# obd_driver_module.net
KiCad netlist of a schematic drawn in EAGLE
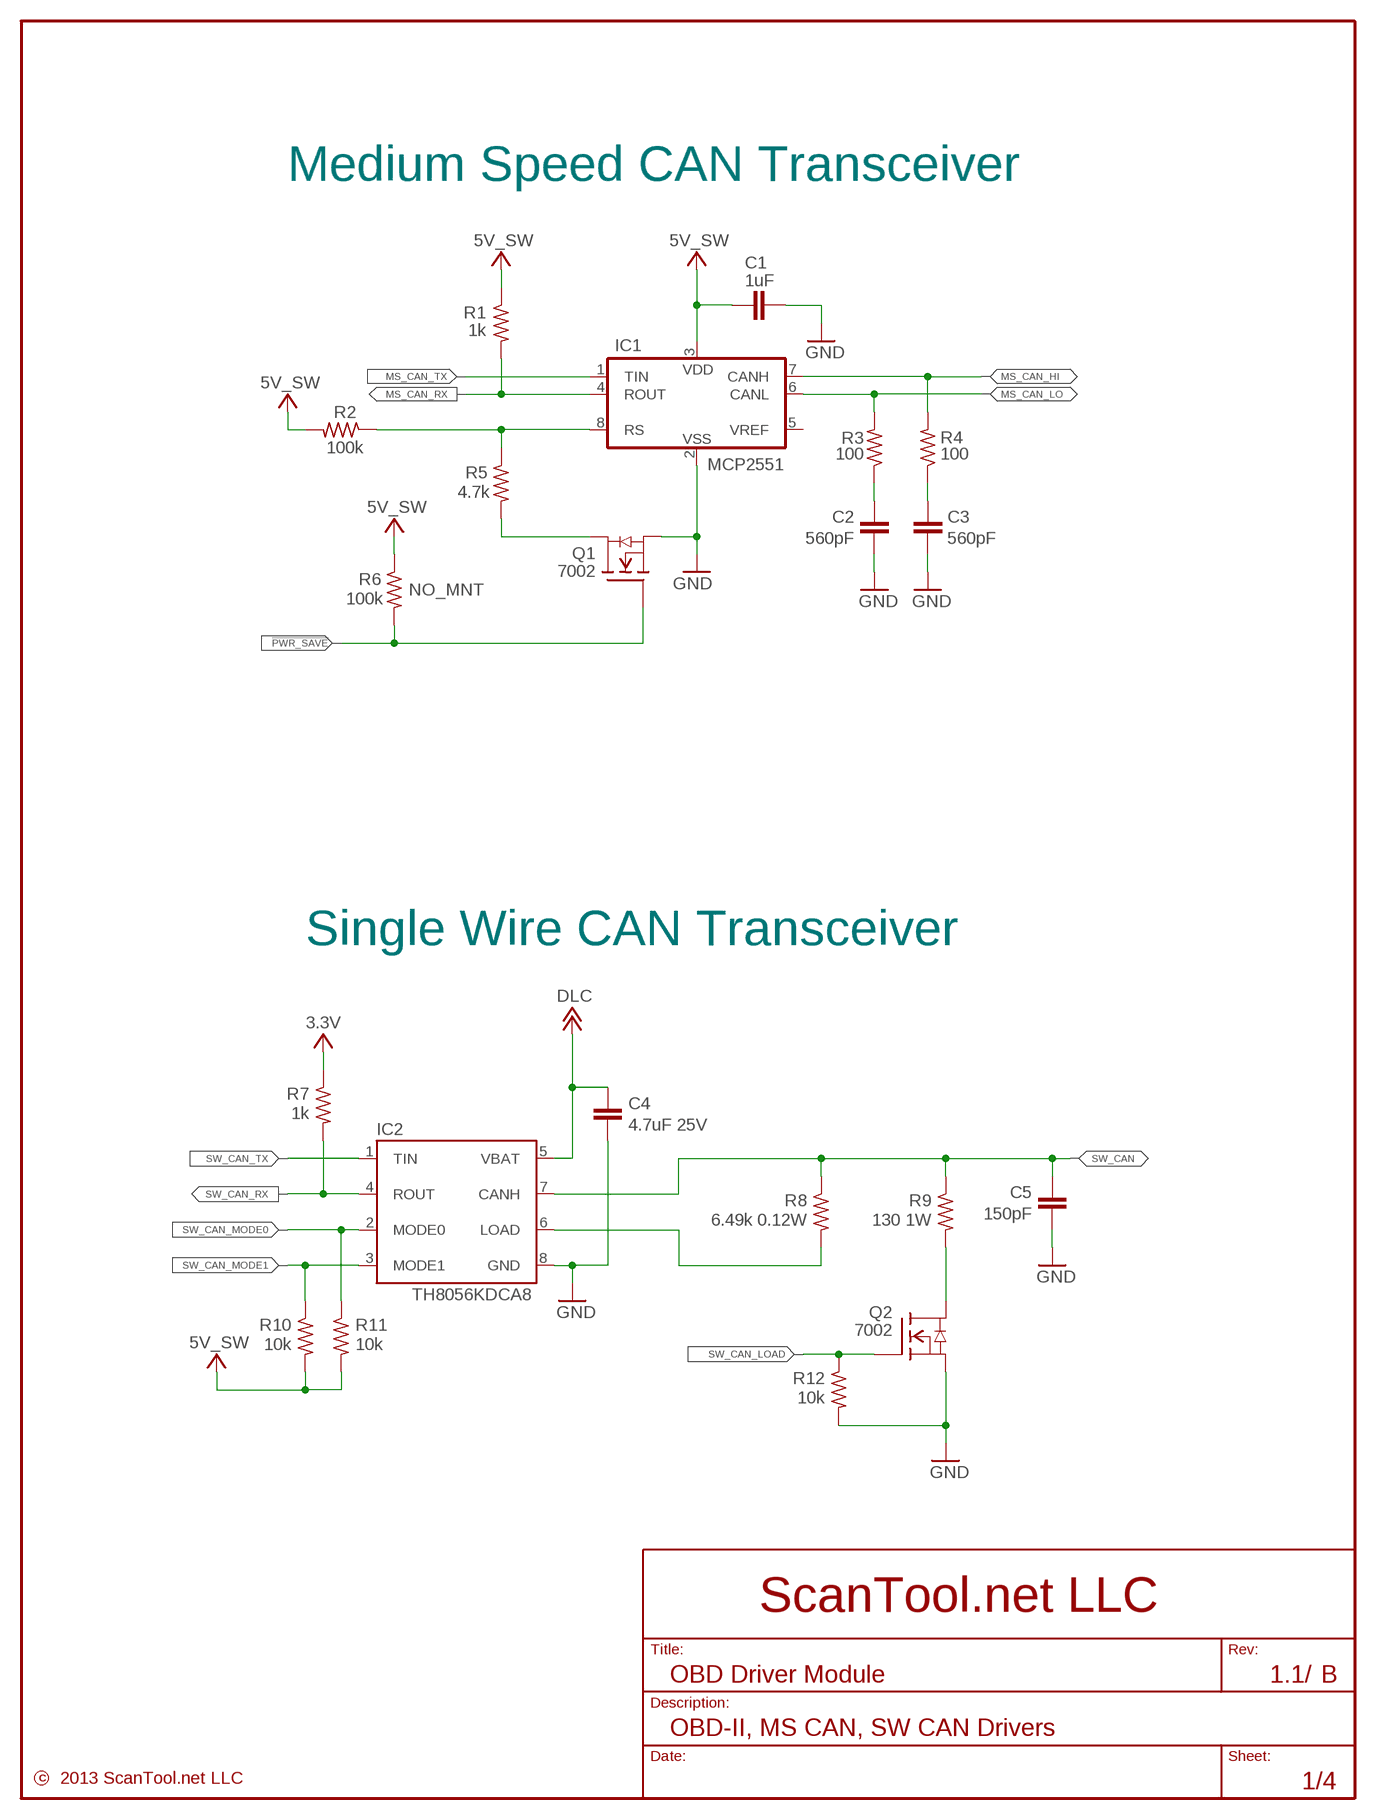
[diagram p0: schematic, sheet 1]
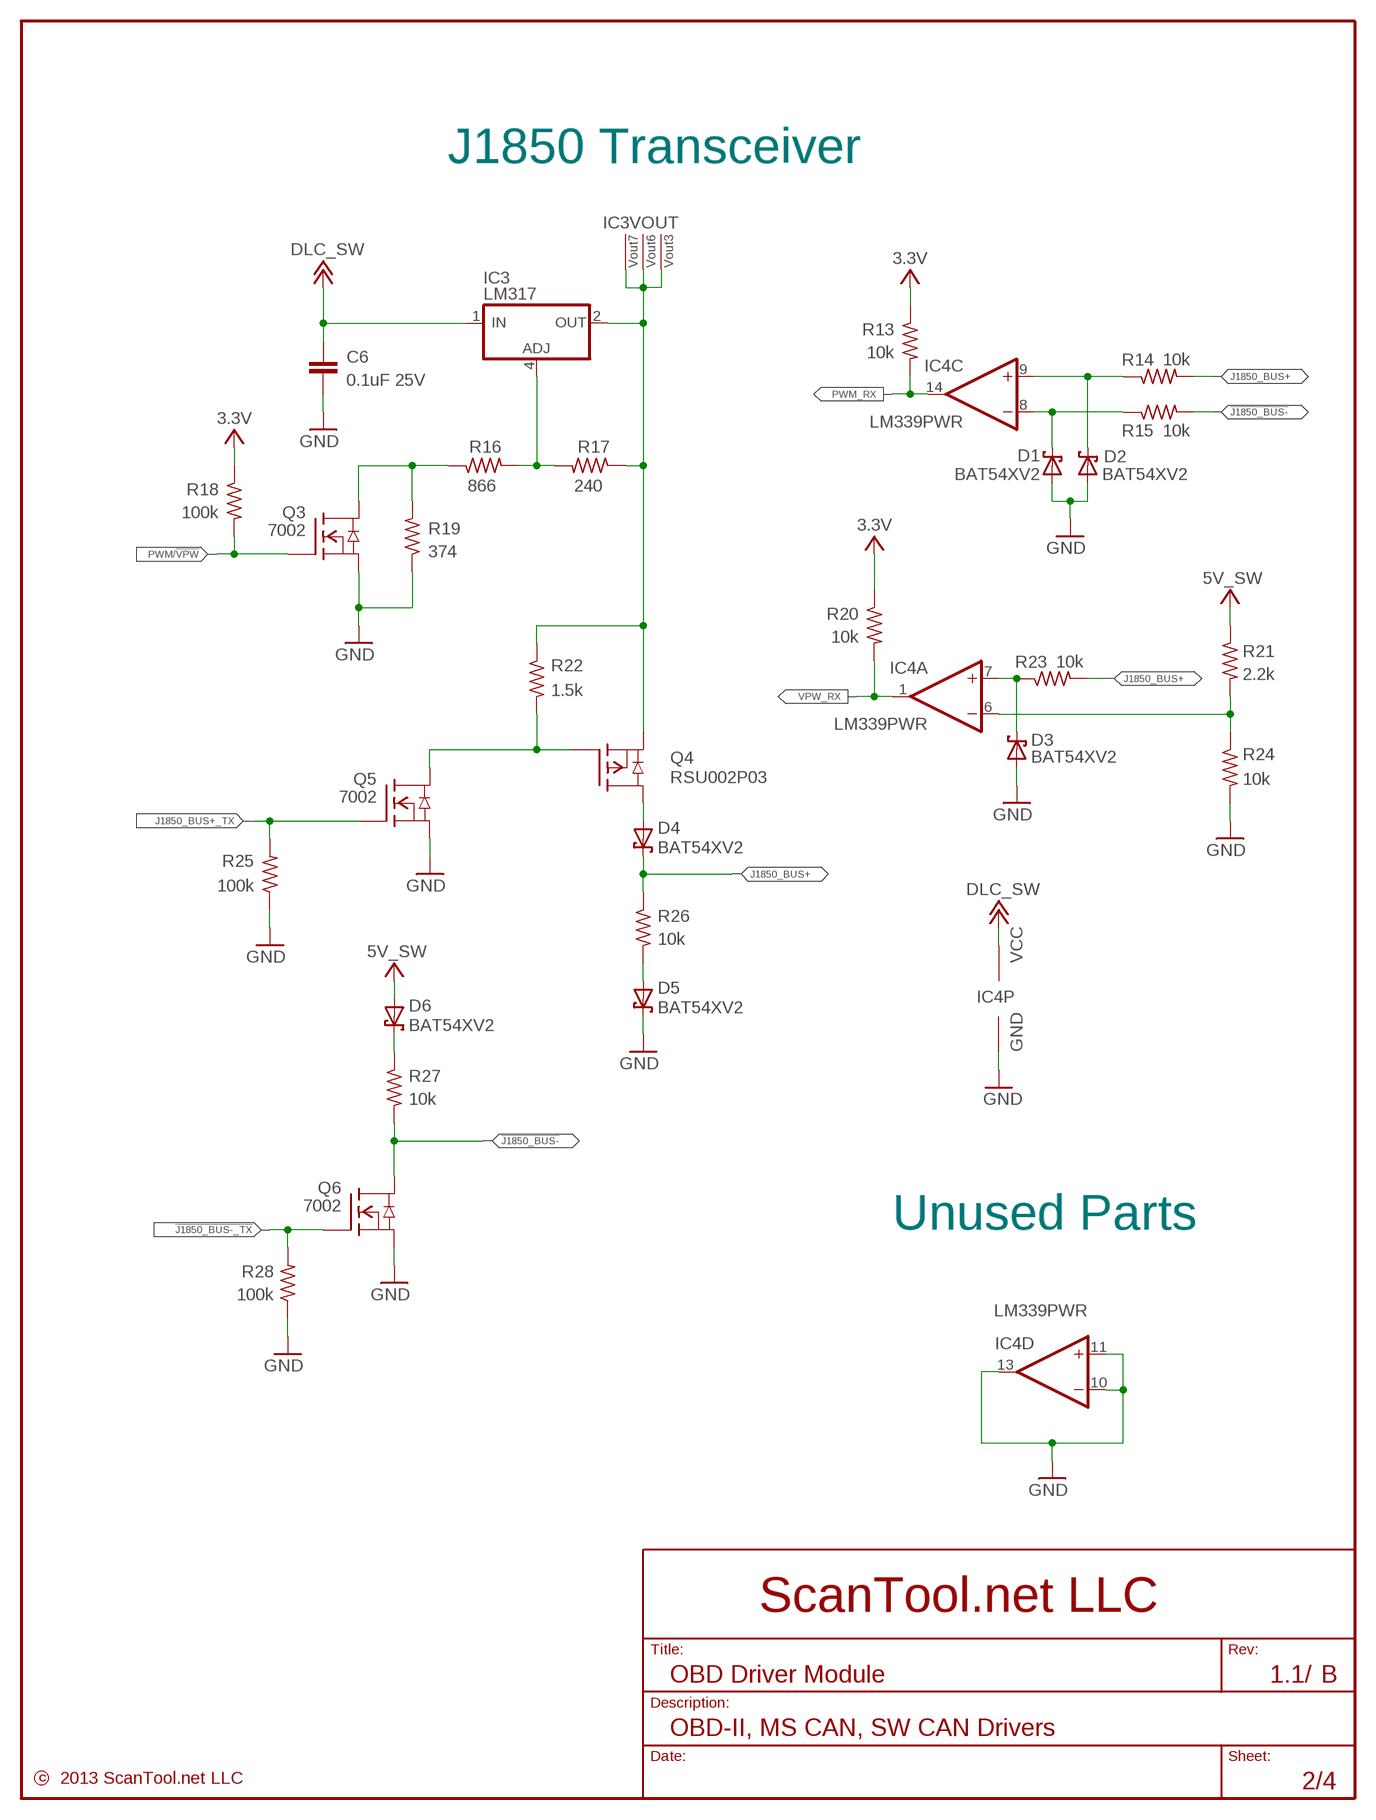
[diagram p1: schematic, sheet 2]
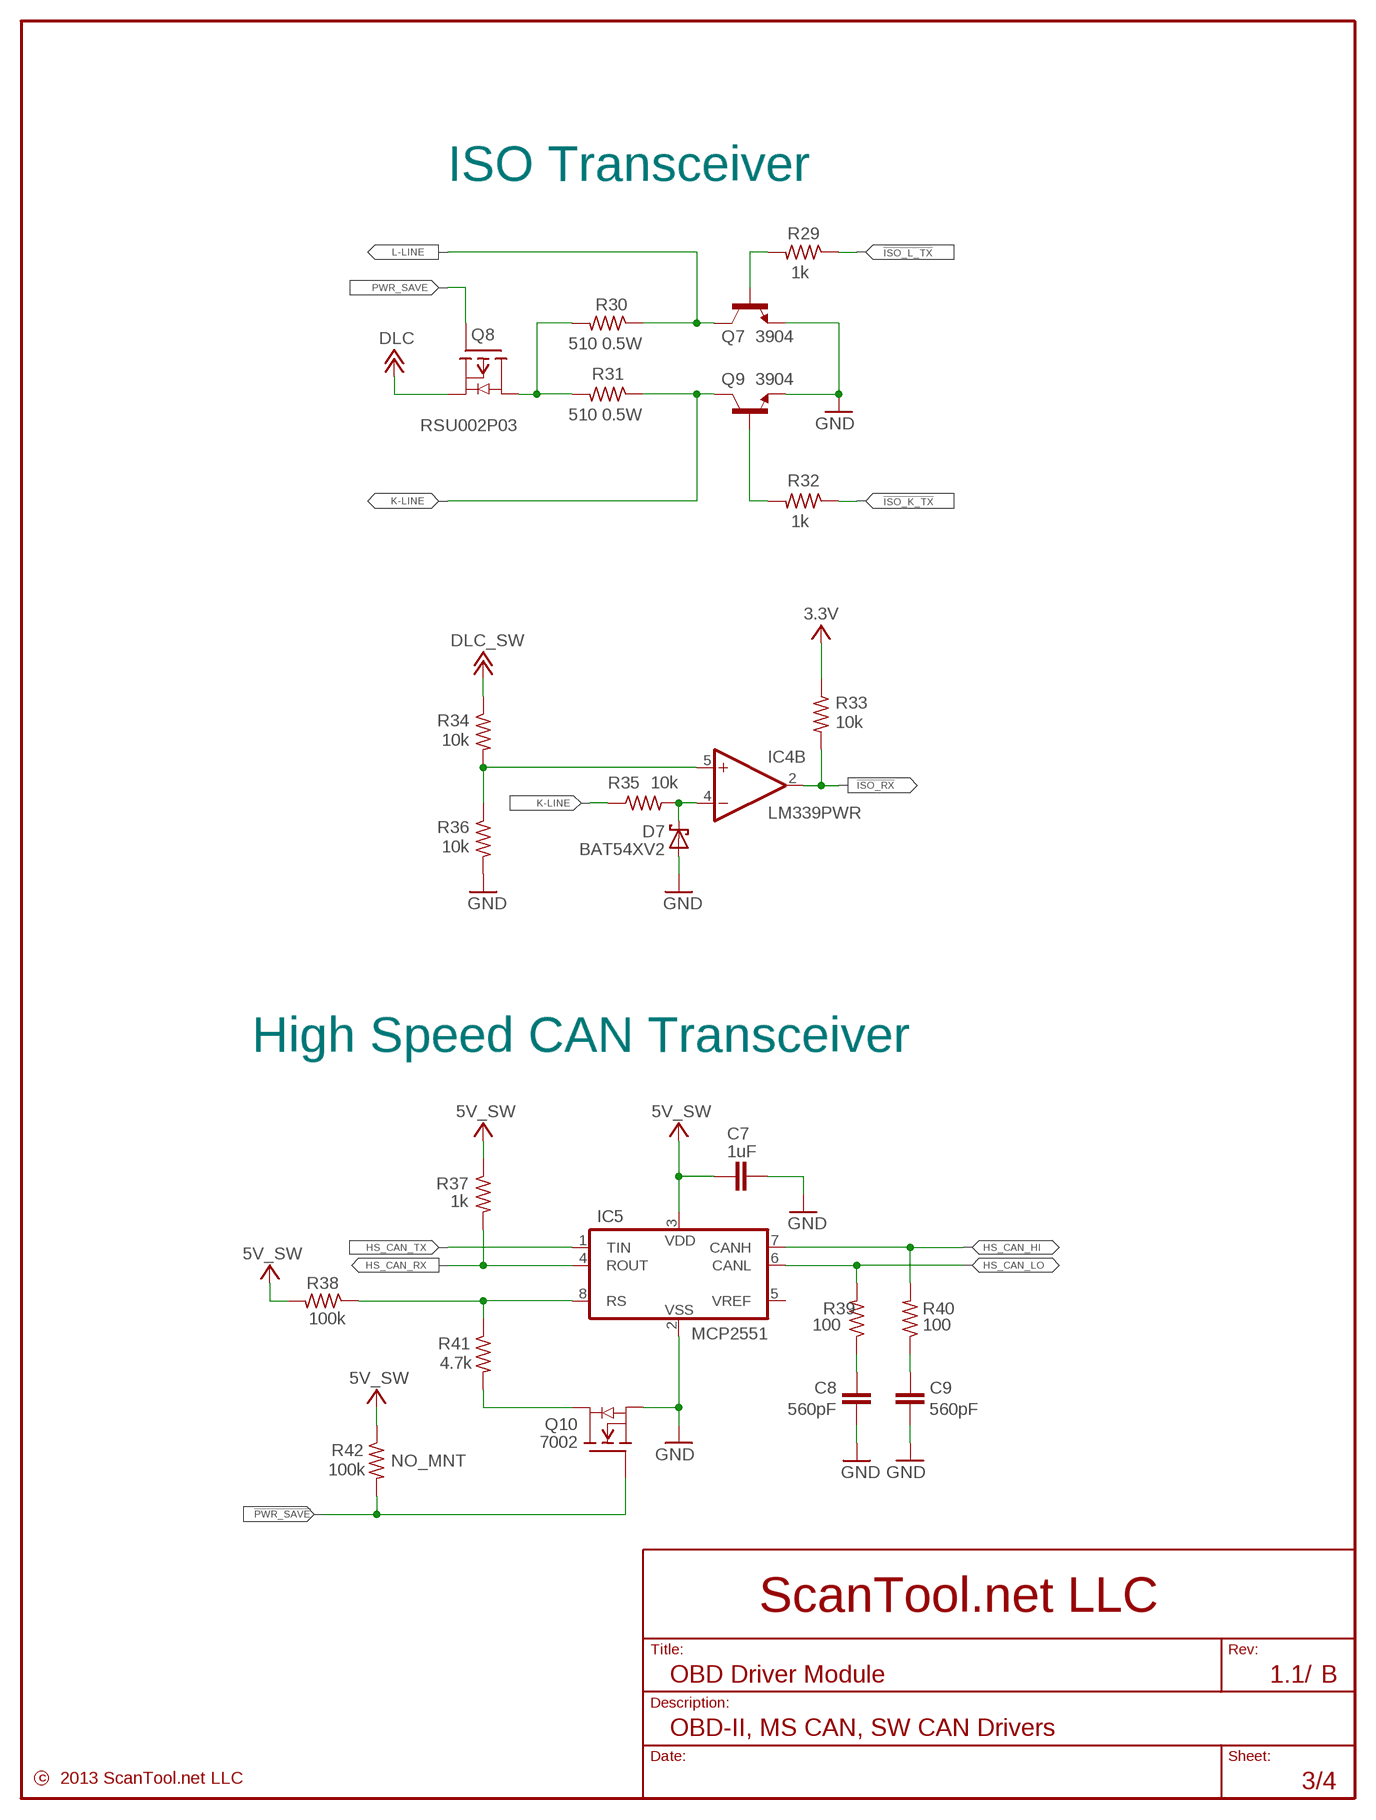
[diagram p2: schematic, sheet 3]
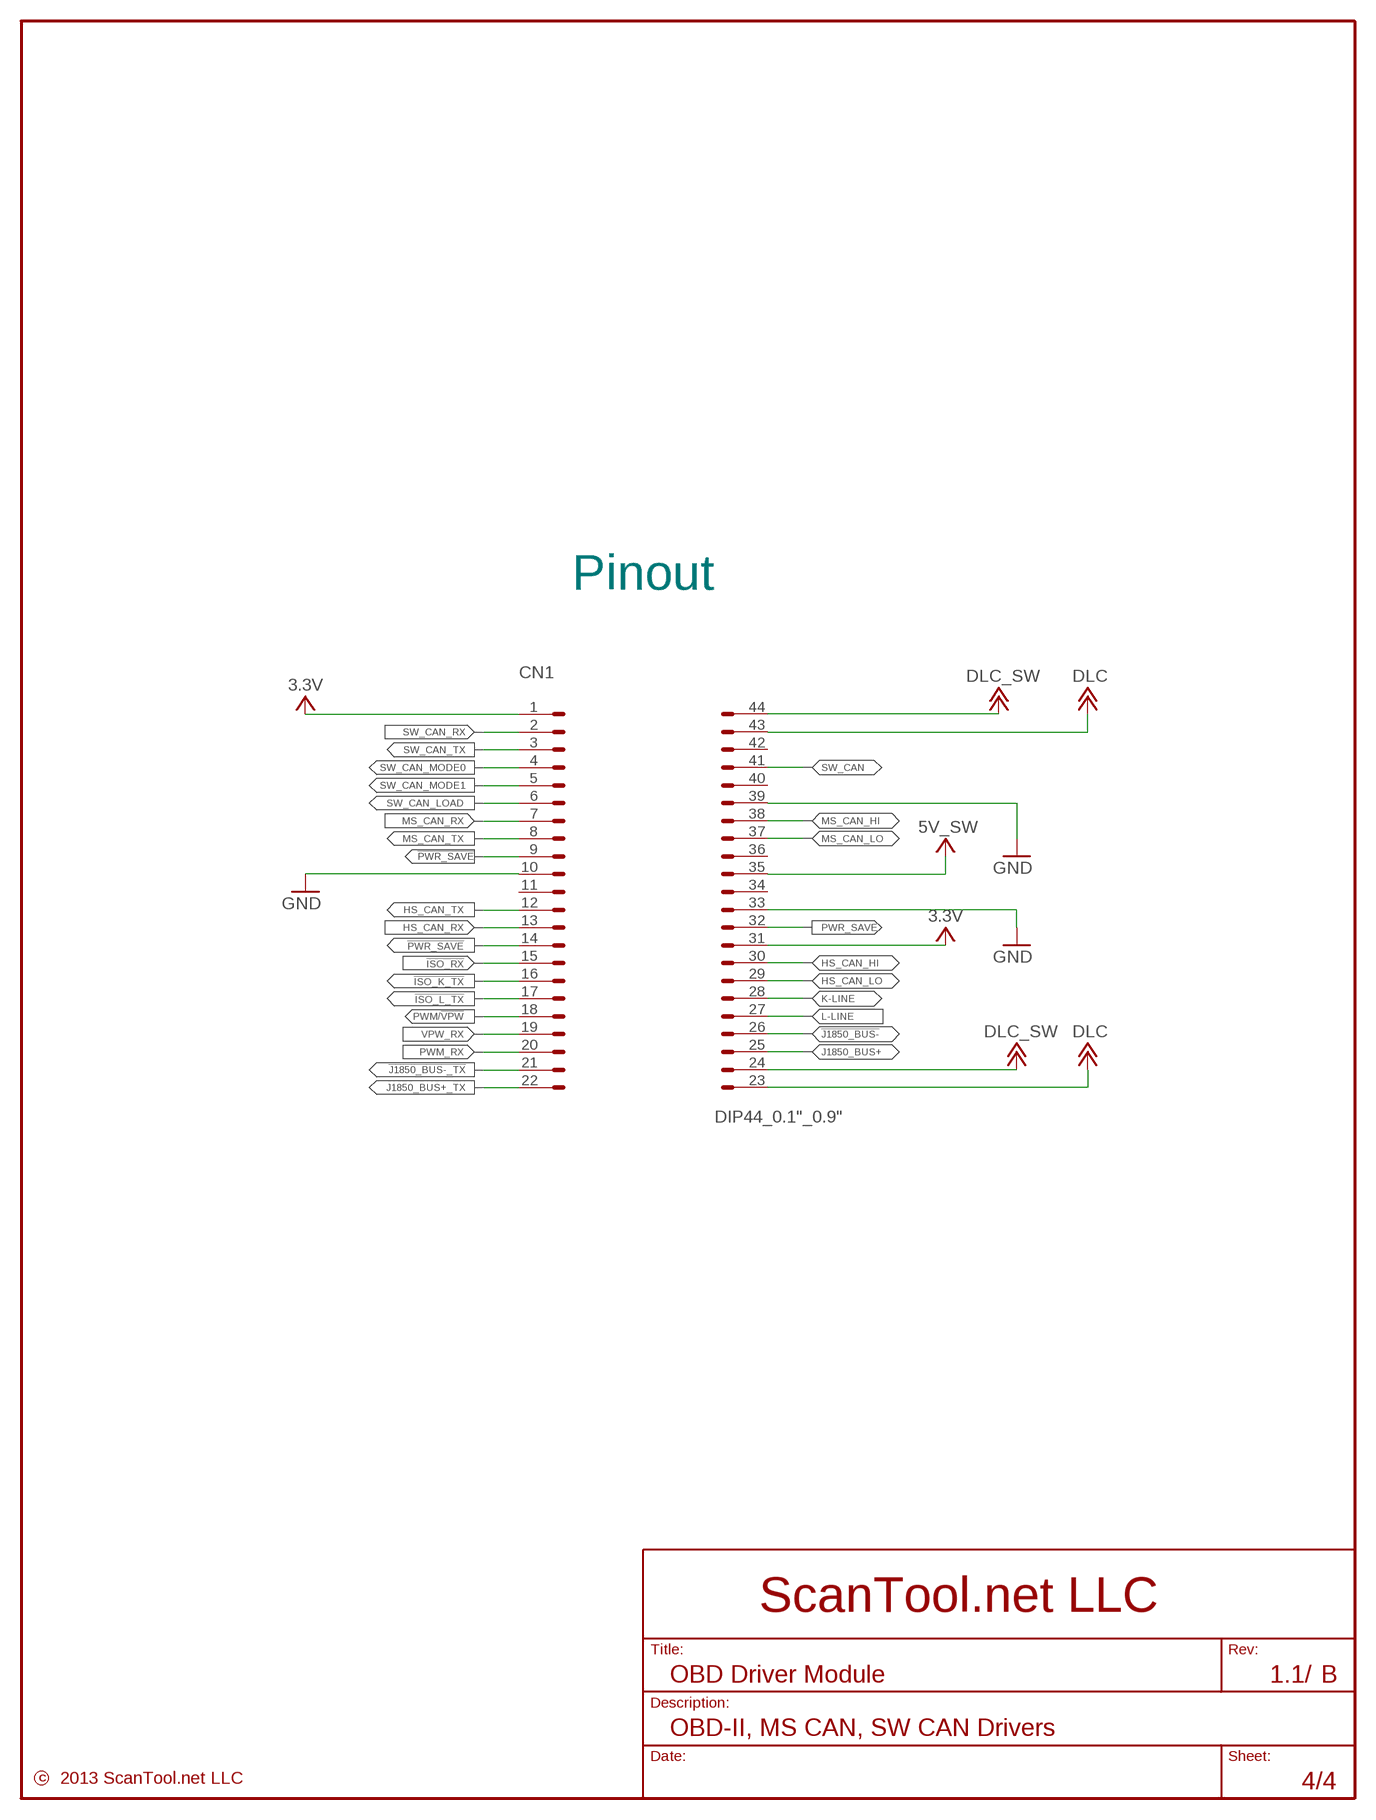
[diagram p3: schematic, sheet 4]

(export (version "E")
  (design (tool "Eeschema 10.0.6"))
  (components
    (comp (ref "C1")
      (value "1uF")
      (footprint "eagle-import:0603")
      (libsource (lib "eagle-import") (part "C-EU_0603"))
    )
    (comp (ref "C2")
      (value "560pF")
      (footprint "eagle-import:0603")
      (libsource (lib "eagle-import") (part "C-EU_0603"))
    )
    (comp (ref "C3")
      (value "560pF")
      (footprint "eagle-import:0603")
      (libsource (lib "eagle-import") (part "C-EU_0603"))
    )
    (comp (ref "C4")
      (value "4.7uF 25V")
      (footprint "eagle-import:0805")
      (libsource (lib "eagle-import") (part "C-EU_0805"))
    )
    (comp (ref "C5")
      (value "150pF")
      (footprint "eagle-import:0603")
      (libsource (lib "eagle-import") (part "C-EU_0603"))
    )
    (comp (ref "IC1")
      (value "MCP2551")
      (footprint "eagle-import:SO-8")
      (fields (field (name "PARTNUM") "MCP2551-I/SN"))
      (libsource (lib "eagle-import") (part "MCP2551-I/SN"))
    )
    (comp (ref "IC2")
      (value "TH8056KDCA8")
      (footprint "eagle-import:SO-8")
      (libsource (lib "eagle-import") (part "TH8056KDCA8"))
    )
    (comp (ref "Q1")
      (value "7002")
      (footprint "eagle-import:SOT323-3")
      (fields
        (field (name "PARTNUM") "2N7002WT1G")
        (field (name "MANUF") "ON Semiconductor")
        (field (name "PARTNUM_1") "2N7002WT1G")
        (field (name "SUPPLIER") "Digikey:2N7002WT1GOSCT-ND")
      )
      (libsource (lib "eagle-import") (part "2N7002W"))
    )
    (comp (ref "Q2")
      (value "7002")
      (footprint "eagle-import:SOT323-3")
      (fields
        (field (name "PARTNUM") "2N7002WT1G")
        (field (name "MANUF") "ON Semiconductor")
        (field (name "PARTNUM_1") "2N7002WT1G")
        (field (name "SUPPLIER") "Digikey:2N7002WT1GOSCT-ND")
      )
      (libsource (lib "eagle-import") (part "2N7002W"))
    )
    (comp (ref "R1")
      (value "1k")
      (footprint "eagle-import:0603")
      (libsource (lib "eagle-import") (part "R-US_0603"))
    )
    (comp (ref "R2")
      (value "100k")
      (footprint "eagle-import:0603")
      (libsource (lib "eagle-import") (part "R-US_0603"))
    )
    (comp (ref "R3")
      (value "100")
      (footprint "eagle-import:0603")
      (libsource (lib "eagle-import") (part "R-US_0603"))
    )
    (comp (ref "R4")
      (value "100")
      (footprint "eagle-import:0603")
      (libsource (lib "eagle-import") (part "R-US_0603"))
    )
    (comp (ref "R5")
      (value "4.7k")
      (footprint "eagle-import:0603")
      (libsource (lib "eagle-import") (part "R-US_0603"))
    )
    (comp (ref "R6")
      (value "100k")
      (footprint "eagle-import:0603")
      (libsource (lib "eagle-import") (part "R-US_0603"))
    )
    (comp (ref "R7")
      (value "1k")
      (footprint "eagle-import:0603")
      (libsource (lib "eagle-import") (part "R-US_0603"))
    )
    (comp (ref "R8")
      (value "6.49k 0.12W")
      (footprint "eagle-import:0603")
      (libsource (lib "eagle-import") (part "R-US_0603"))
    )
    (comp (ref "R9")
      (value "130 1W")
      (footprint "eagle-import:2512")
      (libsource (lib "eagle-import") (part "R-US_2512"))
    )
    (comp (ref "R10")
      (value "10k")
      (footprint "eagle-import:0603")
      (libsource (lib "eagle-import") (part "R-US_0603"))
    )
    (comp (ref "R11")
      (value "10k")
      (footprint "eagle-import:0603")
      (libsource (lib "eagle-import") (part "R-US_0603"))
    )
    (comp (ref "R12")
      (value "10k")
      (footprint "eagle-import:0603")
      (libsource (lib "eagle-import") (part "R-US_0603"))
    )
    (comp (ref "C7")
      (value "1uF")
      (footprint "eagle-import:0603")
      (libsource (lib "eagle-import") (part "C-EU_0603"))
    )
    (comp (ref "C8")
      (value "560pF")
      (footprint "eagle-import:0603")
      (libsource (lib "eagle-import") (part "C-EU_0603"))
    )
    (comp (ref "C9")
      (value "560pF")
      (footprint "eagle-import:0603")
      (libsource (lib "eagle-import") (part "C-EU_0603"))
    )
    (comp (ref "D7")
      (value "BAT54XV2")
      (footprint "eagle-import:SOD-523F")
      (libsource (lib "eagle-import") (part "BAT54XV2"))
    )
    (comp (ref "IC4")
      (value "LM339PWR")
      (footprint "eagle-import:TSSOP-14")
      (libsource (lib "eagle-import") (part "LM339PWR"))
    )
    (comp (ref "IC5")
      (value "MCP2551")
      (footprint "eagle-import:SO-8")
      (fields (field (name "PARTNUM") "MCP2551-I/SN"))
      (libsource (lib "eagle-import") (part "MCP2551-I/SN"))
    )
    (comp (ref "Q7")
      (value "3904")
      (footprint "eagle-import:SOT323-3")
      (fields (field (name "PARTNUM") "MMBT3904WT1G"))
      (libsource (lib "eagle-import") (part "?3904MMST"))
    )
    (comp (ref "Q8")
      (value "RSU002P03")
      (footprint "eagle-import:SOT323-3")
      (fields (field (name "PARTNUM") "RSU002P03T106"))
      (libsource (lib "eagle-import") (part "RSU002P03"))
    )
    (comp (ref "Q9")
      (value "3904")
      (footprint "eagle-import:SOT323-3")
      (fields (field (name "PARTNUM") "MMBT3904WT1G"))
      (libsource (lib "eagle-import") (part "?3904MMST"))
    )
    (comp (ref "Q10")
      (value "7002")
      (footprint "eagle-import:SOT323-3")
      (fields
        (field (name "PARTNUM") "2N7002WT1G")
        (field (name "MANUF") "ON Semiconductor")
        (field (name "PARTNUM_1") "2N7002WT1G")
        (field (name "SUPPLIER") "Digikey:2N7002WT1GOSCT-ND")
      )
      (libsource (lib "eagle-import") (part "2N7002W"))
    )
    (comp (ref "R29")
      (value "1k")
      (footprint "eagle-import:0603")
      (libsource (lib "eagle-import") (part "R-US_0603"))
    )
    (comp (ref "R30")
      (value "510 0.5W")
      (footprint "eagle-import:1210")
      (libsource (lib "eagle-import") (part "R-US_1210"))
    )
    (comp (ref "R31")
      (value "510 0.5W")
      (footprint "eagle-import:1210")
      (libsource (lib "eagle-import") (part "R-US_1210"))
    )
    (comp (ref "R32")
      (value "1k")
      (footprint "eagle-import:0603")
      (libsource (lib "eagle-import") (part "R-US_0603"))
    )
    (comp (ref "R33")
      (value "10k")
      (footprint "eagle-import:0603")
      (libsource (lib "eagle-import") (part "R-US_0603"))
    )
    (comp (ref "R34")
      (value "10k")
      (footprint "eagle-import:0603")
      (libsource (lib "eagle-import") (part "R-US_0603"))
    )
    (comp (ref "R35")
      (value "10k")
      (footprint "eagle-import:0603")
      (libsource (lib "eagle-import") (part "R-US_0603"))
    )
    (comp (ref "R36")
      (value "10k")
      (footprint "eagle-import:0603")
      (libsource (lib "eagle-import") (part "R-US_0603"))
    )
    (comp (ref "R37")
      (value "1k")
      (footprint "eagle-import:0603")
      (libsource (lib "eagle-import") (part "R-US_0603"))
    )
    (comp (ref "R38")
      (value "100k")
      (footprint "eagle-import:0603")
      (libsource (lib "eagle-import") (part "R-US_0603"))
    )
    (comp (ref "R39")
      (value "100")
      (footprint "eagle-import:0603")
      (libsource (lib "eagle-import") (part "R-US_0603"))
    )
    (comp (ref "R40")
      (value "100")
      (footprint "eagle-import:0603")
      (libsource (lib "eagle-import") (part "R-US_0603"))
    )
    (comp (ref "R41")
      (value "4.7k")
      (footprint "eagle-import:0603")
      (libsource (lib "eagle-import") (part "R-US_0603"))
    )
    (comp (ref "R42")
      (value "100k")
      (footprint "eagle-import:0603")
      (libsource (lib "eagle-import") (part "R-US_0603"))
    )
    (comp (ref "C6")
      (value "0.1uF 25V")
      (footprint "eagle-import:0603")
      (libsource (lib "eagle-import") (part "C-EU_0603"))
    )
    (comp (ref "D1")
      (value "BAT54XV2")
      (footprint "eagle-import:SOD-523F")
      (fields
        (field (name "DESC") "Diode, Schottky")
        (field (name "MANUF") "Fairchild")
        (field (name "PARTNUM") "BAT54XV2")
        (field (name "SUPPLIER") "Digikey:BAT54XV2TR-ND")
        (field (name "VALSTAT") "PARTNUM")
      )
      (libsource (lib "eagle-import") (part "BAT54XV2"))
    )
    (comp (ref "D2")
      (value "BAT54XV2")
      (footprint "eagle-import:SOD-523F")
      (fields
        (field (name "DESC") "Diode, Schottky")
        (field (name "MANUF") "Fairchild")
        (field (name "PARTNUM") "BAT54XV2")
        (field (name "SUPPLIER") "Digikey:BAT54XV2TR-ND")
        (field (name "VALSTAT") "PARTNUM")
      )
      (libsource (lib "eagle-import") (part "BAT54XV2"))
    )
    (comp (ref "D3")
      (value "BAT54XV2")
      (footprint "eagle-import:SOD-523F")
      (fields
        (field (name "DESC") "Diode, Schottky")
        (field (name "MANUF") "Fairchild")
        (field (name "PARTNUM") "BAT54XV2")
        (field (name "SUPPLIER") "Digikey:BAT54XV2TR-ND")
        (field (name "VALSTAT") "PARTNUM")
      )
      (libsource (lib "eagle-import") (part "BAT54XV2"))
    )
    (comp (ref "D4")
      (value "BAT54XV2")
      (footprint "eagle-import:SOD-523F")
      (libsource (lib "eagle-import") (part "BAT54XV2"))
    )
    (comp (ref "D5")
      (value "BAT54XV2")
      (footprint "eagle-import:SOD-523F")
      (libsource (lib "eagle-import") (part "BAT54XV2"))
    )
    (comp (ref "D6")
      (value "BAT54XV2")
      (footprint "eagle-import:SOD-523F")
      (libsource (lib "eagle-import") (part "BAT54XV2"))
    )
    (comp (ref "IC3")
      (value "LM317")
      (footprint "eagle-import:TSSOP-8")
      (fields (field (name "PARTNUM") "LM317LCPWR"))
      (libsource (lib "eagle-import") (part "LM317L?PWC"))
    )
    (comp (ref "Q3")
      (value "7002")
      (footprint "eagle-import:SOT323-3")
      (fields
        (field (name "PARTNUM") "2N7002WT1G")
        (field (name "MANUF") "ON Semiconductor")
        (field (name "PARTNUM_1") "2N7002WT1G")
        (field (name "SUPPLIER") "Digikey:2N7002WT1GOSCT-ND")
      )
      (libsource (lib "eagle-import") (part "2N7002W"))
    )
    (comp (ref "Q4")
      (value "RSU002P03")
      (footprint "eagle-import:SOT323-3")
      (fields (field (name "PARTNUM") "RSU002P03T106"))
      (libsource (lib "eagle-import") (part "RSU002P03"))
    )
    (comp (ref "Q5")
      (value "7002")
      (footprint "eagle-import:SOT323-3")
      (fields
        (field (name "PARTNUM") "2N7002WT1G")
        (field (name "MANUF") "ON Semiconductor")
        (field (name "PARTNUM_1") "2N7002WT1G")
        (field (name "SUPPLIER") "Digikey:2N7002WT1GOSCT-ND")
      )
      (libsource (lib "eagle-import") (part "2N7002W"))
    )
    (comp (ref "Q6")
      (value "7002")
      (footprint "eagle-import:SOT323-3")
      (fields
        (field (name "PARTNUM") "2N7002WT1G")
        (field (name "MANUF") "ON Semiconductor")
        (field (name "PARTNUM_1") "2N7002WT1G")
        (field (name "SUPPLIER") "Digikey:2N7002WT1GOSCT-ND")
      )
      (libsource (lib "eagle-import") (part "2N7002W"))
    )
    (comp (ref "R13")
      (value "10k")
      (footprint "eagle-import:0603")
      (libsource (lib "eagle-import") (part "R-US_0603"))
    )
    (comp (ref "R14")
      (value "10k")
      (footprint "eagle-import:0603")
      (libsource (lib "eagle-import") (part "R-US_0603"))
    )
    (comp (ref "R15")
      (value "10k")
      (footprint "eagle-import:0603")
      (libsource (lib "eagle-import") (part "R-US_0603"))
    )
    (comp (ref "R16")
      (value "866")
      (footprint "eagle-import:0603")
      (libsource (lib "eagle-import") (part "R-US_0603"))
    )
    (comp (ref "R17")
      (value "240")
      (footprint "eagle-import:0603")
      (libsource (lib "eagle-import") (part "R-US_0603"))
    )
    (comp (ref "R18")
      (value "100k")
      (footprint "eagle-import:0603")
      (libsource (lib "eagle-import") (part "R-US_0603"))
    )
    (comp (ref "R19")
      (value "374")
      (footprint "eagle-import:0603")
      (libsource (lib "eagle-import") (part "R-US_0603"))
    )
    (comp (ref "R20")
      (value "10k")
      (footprint "eagle-import:0603")
      (libsource (lib "eagle-import") (part "R-US_0603"))
    )
    (comp (ref "R21")
      (value "2.2k")
      (footprint "eagle-import:0603")
      (libsource (lib "eagle-import") (part "R-US_0603"))
    )
    (comp (ref "R22")
      (value "1.5k")
      (footprint "eagle-import:0603")
      (libsource (lib "eagle-import") (part "R-US_0603"))
    )
    (comp (ref "R23")
      (value "10k")
      (footprint "eagle-import:0603")
      (libsource (lib "eagle-import") (part "R-US_0603"))
    )
    (comp (ref "R24")
      (value "10k")
      (footprint "eagle-import:0603")
      (libsource (lib "eagle-import") (part "R-US_0603"))
    )
    (comp (ref "R25")
      (value "100k")
      (footprint "eagle-import:0603")
      (libsource (lib "eagle-import") (part "R-US_0603"))
    )
    (comp (ref "R26")
      (value "10k")
      (footprint "eagle-import:0603")
      (libsource (lib "eagle-import") (part "R-US_0603"))
    )
    (comp (ref "R27")
      (value "10k")
      (footprint "eagle-import:0603")
      (libsource (lib "eagle-import") (part "R-US_0603"))
    )
    (comp (ref "R28")
      (value "100k")
      (footprint "eagle-import:0603")
      (libsource (lib "eagle-import") (part "R-US_0603"))
    )
    (comp (ref "CN1")
      (value "DIP44_0.1\"_0.9\"")
      (footprint "eagle-import:DIP44_0.1__0.9_")
      (fields (field (name "PARTNUM") "DIP 44 Pin Socket"))
      (libsource (lib "eagle-import") (part "DIP44_0.1{dblquote}_0.9{dblquote}"))
    )
  )
  (nets
    (net (code "1") (name "3.3V") (class "Default")
      (node (ref "CN1") (pin "1") (pinfunction "1_1") (pintype "passive"))
      (node (ref "CN1") (pin "31") (pinfunction "31_31") (pintype "passive"))
      (node (ref "R13") (pin "1") (pinfunction "1_1") (pintype "passive"))
      (node (ref "R18") (pin "1") (pinfunction "1_1") (pintype "passive"))
      (node (ref "R20") (pin "1") (pinfunction "1_1") (pintype "passive"))
      (node (ref "R33") (pin "1") (pinfunction "1_1") (pintype "passive"))
      (node (ref "R7") (pin "1") (pinfunction "1_1") (pintype "passive"))
    )
    (net (code "2") (name "5V_SW") (class "Default")
      (node (ref "C1") (pin "1") (pinfunction "1_1") (pintype "passive"))
      (node (ref "C7") (pin "1") (pinfunction "1_1") (pintype "passive"))
      (node (ref "CN1") (pin "35") (pinfunction "35_35") (pintype "passive"))
      (node (ref "D6") (pin "A") (pinfunction "A_A") (pintype "passive"))
      (node (ref "IC1") (pin "3") (pinfunction "VDD_3") (pintype "power_in"))
      (node (ref "IC5") (pin "3") (pinfunction "VDD_3") (pintype "power_in"))
      (node (ref "R1") (pin "1") (pinfunction "1_1") (pintype "passive"))
      (node (ref "R10") (pin "2") (pinfunction "2_2") (pintype "passive"))
      (node (ref "R11") (pin "2") (pinfunction "2_2") (pintype "passive"))
      (node (ref "R2") (pin "2") (pinfunction "2_2") (pintype "passive"))
      (node (ref "R21") (pin "1") (pinfunction "1_1") (pintype "passive"))
      (node (ref "R37") (pin "1") (pinfunction "1_1") (pintype "passive"))
      (node (ref "R38") (pin "2") (pinfunction "2_2") (pintype "passive"))
      (node (ref "R42") (pin "1") (pinfunction "1_1") (pintype "passive"))
      (node (ref "R6") (pin "1") (pinfunction "1_1") (pintype "passive"))
    )
    (net (code "3") (name "DLC") (class "Default")
      (node (ref "C4") (pin "2") (pinfunction "2_2") (pintype "passive"))
      (node (ref "CN1") (pin "23") (pinfunction "23_23") (pintype "passive"))
      (node (ref "CN1") (pin "43") (pinfunction "43_43") (pintype "passive"))
      (node (ref "IC2") (pin "5") (pinfunction "VBAT_5") (pintype "power_in"))
      (node (ref "Q8") (pin "2") (pinfunction "S_2") (pintype "passive"))
    )
    (net (code "4") (name "DLC_SW") (class "Default")
      (node (ref "C6") (pin "1") (pinfunction "1_1") (pintype "passive"))
      (node (ref "CN1") (pin "24") (pinfunction "24_24") (pintype "passive"))
      (node (ref "CN1") (pin "44") (pinfunction "44_44") (pintype "passive"))
      (node (ref "IC3") (pin "1") (pinfunction "IN_1") (pintype "input"))
      (node (ref "IC4") (pin "3") (pinfunction "VCC_3") (pintype "power_in"))
      (node (ref "R34") (pin "1") (pinfunction "1_1") (pintype "passive"))
    )
    (net (code "5") (name "GND") (class "Default")
      (node (ref "C1") (pin "2") (pinfunction "2_2") (pintype "passive"))
      (node (ref "C2") (pin "2") (pinfunction "2_2") (pintype "passive"))
      (node (ref "C3") (pin "2") (pinfunction "2_2") (pintype "passive"))
      (node (ref "C4") (pin "1") (pinfunction "1_1") (pintype "passive"))
      (node (ref "C5") (pin "1") (pinfunction "1_1") (pintype "passive"))
      (node (ref "C6") (pin "2") (pinfunction "2_2") (pintype "passive"))
      (node (ref "C7") (pin "2") (pinfunction "2_2") (pintype "passive"))
      (node (ref "C8") (pin "2") (pinfunction "2_2") (pintype "passive"))
      (node (ref "C9") (pin "2") (pinfunction "2_2") (pintype "passive"))
      (node (ref "CN1") (pin "10") (pinfunction "10_10") (pintype "passive"))
      (node (ref "CN1") (pin "33") (pinfunction "33_33") (pintype "passive"))
      (node (ref "CN1") (pin "39") (pinfunction "39_39") (pintype "passive"))
      (node (ref "D1") (pin "A") (pinfunction "A_A") (pintype "passive"))
      (node (ref "D2") (pin "A") (pinfunction "A_A") (pintype "passive"))
      (node (ref "D3") (pin "A") (pinfunction "A_A") (pintype "passive"))
      (node (ref "D5") (pin "C") (pinfunction "C_C") (pintype "passive"))
      (node (ref "D7") (pin "A") (pinfunction "A_A") (pintype "passive"))
      (node (ref "IC1") (pin "2") (pinfunction "VSS_2") (pintype "power_in"))
      (node (ref "IC2") (pin "8") (pinfunction "GND_8") (pintype "power_in"))
      (node (ref "IC4") (pin "10") (pinfunction "-IN_10") (pintype "input"))
      (node (ref "IC4") (pin "11") (pinfunction "+IN_11") (pintype "input"))
      (node (ref "IC4") (pin "12") (pinfunction "GND_12") (pintype "power_in"))
      (node (ref "IC4") (pin "13") (pinfunction "OUT_13") (pintype "open_collector"))
      (node (ref "IC5") (pin "2") (pinfunction "VSS_2") (pintype "power_in"))
      (node (ref "Q1") (pin "2") (pinfunction "S_2") (pintype "passive"))
      (node (ref "Q10") (pin "2") (pinfunction "S_2") (pintype "passive"))
      (node (ref "Q2") (pin "2") (pinfunction "S_2") (pintype "passive"))
      (node (ref "Q3") (pin "2") (pinfunction "S_2") (pintype "passive"))
      (node (ref "Q5") (pin "2") (pinfunction "S_2") (pintype "passive"))
      (node (ref "Q6") (pin "2") (pinfunction "S_2") (pintype "passive"))
      (node (ref "Q7") (pin "2") (pinfunction "E_2") (pintype "passive"))
      (node (ref "Q9") (pin "2") (pinfunction "E_2") (pintype "passive"))
      (node (ref "R12") (pin "2") (pinfunction "2_2") (pintype "passive"))
      (node (ref "R19") (pin "1") (pinfunction "1_1") (pintype "passive"))
      (node (ref "R24") (pin "2") (pinfunction "2_2") (pintype "passive"))
      (node (ref "R25") (pin "1") (pinfunction "1_1") (pintype "passive"))
      (node (ref "R28") (pin "1") (pinfunction "1_1") (pintype "passive"))
      (node (ref "R36") (pin "2") (pinfunction "2_2") (pintype "passive"))
    )
    (net (code "6") (name "HS_CAN_HI") (class "Default")
      (node (ref "CN1") (pin "30") (pinfunction "30_30") (pintype "passive"))
      (node (ref "IC5") (pin "7") (pinfunction "CANH_7") (pintype "bidirectional"))
      (node (ref "R40") (pin "2") (pinfunction "2_2") (pintype "passive"))
    )
    (net (code "7") (name "HS_CAN_LO") (class "Default")
      (node (ref "CN1") (pin "29") (pinfunction "29_29") (pintype "passive"))
      (node (ref "IC5") (pin "6") (pinfunction "CANL_6") (pintype "bidirectional"))
      (node (ref "R39") (pin "2") (pinfunction "2_2") (pintype "passive"))
    )
    (net (code "8") (name "HS_CAN_RX") (class "Default")
      (node (ref "CN1") (pin "13") (pinfunction "13_13") (pintype "passive"))
      (node (ref "IC5") (pin "4") (pinfunction "ROUT_4") (pintype "output"))
      (node (ref "R37") (pin "2") (pinfunction "2_2") (pintype "passive"))
    )
    (net (code "9") (name "HS_CAN_TX") (class "Default")
      (node (ref "CN1") (pin "12") (pinfunction "12_12") (pintype "passive"))
      (node (ref "IC5") (pin "1") (pinfunction "TIN_1") (pintype "input"))
    )
    (net (code "10") (name "J1850_BUS+") (class "Default")
      (node (ref "CN1") (pin "25") (pinfunction "25_25") (pintype "passive"))
      (node (ref "D4") (pin "C") (pinfunction "C_C") (pintype "passive"))
      (node (ref "R14") (pin "2") (pinfunction "2_2") (pintype "passive"))
      (node (ref "R23") (pin "2") (pinfunction "2_2") (pintype "passive"))
      (node (ref "R26") (pin "1") (pinfunction "1_1") (pintype "passive"))
    )
    (net (code "11") (name "J1850_BUS+_TX") (class "Default")
      (node (ref "CN1") (pin "22") (pinfunction "22_22") (pintype "passive"))
      (node (ref "Q5") (pin "1") (pinfunction "G_1") (pintype "passive"))
      (node (ref "R25") (pin "2") (pinfunction "2_2") (pintype "passive"))
    )
    (net (code "12") (name "K-LINE") (class "Default")
      (node (ref "CN1") (pin "28") (pinfunction "28_28") (pintype "passive"))
      (node (ref "Q9") (pin "3") (pinfunction "C_3") (pintype "passive"))
      (node (ref "R31") (pin "1") (pinfunction "1_1") (pintype "passive"))
      (node (ref "R35") (pin "1") (pinfunction "1_1") (pintype "passive"))
    )
    (net (code "13") (name "L-LINE") (class "Default")
      (node (ref "CN1") (pin "27") (pinfunction "27_27") (pintype "passive"))
      (node (ref "Q7") (pin "3") (pinfunction "C_3") (pintype "passive"))
      (node (ref "R30") (pin "1") (pinfunction "1_1") (pintype "passive"))
    )
    (net (code "14") (name "MS_CAN_HI") (class "Default")
      (node (ref "CN1") (pin "38") (pinfunction "38_38") (pintype "passive"))
      (node (ref "IC1") (pin "7") (pinfunction "CANH_7") (pintype "bidirectional"))
      (node (ref "R4") (pin "2") (pinfunction "2_2") (pintype "passive"))
    )
    (net (code "15") (name "MS_CAN_LO") (class "Default")
      (node (ref "CN1") (pin "37") (pinfunction "37_37") (pintype "passive"))
      (node (ref "IC1") (pin "6") (pinfunction "CANL_6") (pintype "bidirectional"))
      (node (ref "R3") (pin "2") (pinfunction "2_2") (pintype "passive"))
    )
    (net (code "16") (name "MS_CAN_RX") (class "Default")
      (node (ref "CN1") (pin "7") (pinfunction "7_7") (pintype "passive"))
      (node (ref "IC1") (pin "4") (pinfunction "ROUT_4") (pintype "output"))
      (node (ref "R1") (pin "2") (pinfunction "2_2") (pintype "passive"))
    )
    (net (code "17") (name "MS_CAN_TX") (class "Default")
      (node (ref "CN1") (pin "8") (pinfunction "8_8") (pintype "passive"))
      (node (ref "IC1") (pin "1") (pinfunction "TIN_1") (pintype "input"))
    )
    (net (code "18") (name "Net-(C2-Pad1)") (class "Default")
      (node (ref "C2") (pin "1") (pinfunction "1_1") (pintype "passive"))
      (node (ref "R3") (pin "1") (pinfunction "1_1") (pintype "passive"))
    )
    (net (code "19") (name "Net-(C3-Pad1)") (class "Default")
      (node (ref "C3") (pin "1") (pinfunction "1_1") (pintype "passive"))
      (node (ref "R4") (pin "1") (pinfunction "1_1") (pintype "passive"))
    )
    (net (code "20") (name "Net-(C8-Pad1)") (class "Default")
      (node (ref "C8") (pin "1") (pinfunction "1_1") (pintype "passive"))
      (node (ref "R39") (pin "1") (pinfunction "1_1") (pintype "passive"))
    )
    (net (code "21") (name "Net-(C9-Pad1)") (class "Default")
      (node (ref "C9") (pin "1") (pinfunction "1_1") (pintype "passive"))
      (node (ref "R40") (pin "1") (pinfunction "1_1") (pintype "passive"))
    )
    (net (code "22") (name "Net-(D5-PadA)") (class "Default")
      (node (ref "D5") (pin "A") (pinfunction "A_A") (pintype "passive"))
      (node (ref "R26") (pin "2") (pinfunction "2_2") (pintype "passive"))
    )
    (net (code "23") (name "Net-(D6-PadC)") (class "Default")
      (node (ref "D6") (pin "C") (pinfunction "C_C") (pintype "passive"))
      (node (ref "R27") (pin "1") (pinfunction "1_1") (pintype "passive"))
    )
    (net (code "24") (name "Net-(IC1-RS)") (class "Default")
      (node (ref "IC1") (pin "8") (pinfunction "RS_8") (pintype "input"))
      (node (ref "R2") (pin "1") (pinfunction "1_1") (pintype "passive"))
      (node (ref "R5") (pin "1") (pinfunction "1_1") (pintype "passive"))
    )
    (net (code "25") (name "Net-(IC2-LOAD)") (class "Default")
      (node (ref "IC2") (pin "6") (pinfunction "LOAD_6") (pintype "output"))
      (node (ref "R8") (pin "2") (pinfunction "2_2") (pintype "passive"))
    )
    (net (code "26") (name "Net-(IC3A-ADJ)") (class "Default")
      (node (ref "IC3") (pin "4") (pinfunction "ADJ_4") (pintype "input"))
      (node (ref "R16") (pin "2") (pinfunction "2_2") (pintype "passive"))
      (node (ref "R17") (pin "2") (pinfunction "2_2") (pintype "passive"))
    )
    (net (code "27") (name "Net-(IC3A-OUT)") (class "Default")
      (node (ref "IC3") (pin "2") (pinfunction "OUT_2") (pintype "power_in"))
      (node (ref "IC3") (pin "3") (pinfunction "OUT_3") (pintype "power_in"))
      (node (ref "IC3") (pin "6") (pinfunction "OUT_6") (pintype "power_in"))
      (node (ref "IC3") (pin "7") (pinfunction "OUT_7") (pintype "power_in"))
      (node (ref "Q4") (pin "2") (pinfunction "S_2") (pintype "passive"))
      (node (ref "R17") (pin "1") (pinfunction "1_1") (pintype "passive"))
      (node (ref "R22") (pin "1") (pinfunction "1_1") (pintype "passive"))
    )
    (net (code "28") (name "Net-(IC4A-+IN)") (class "Default")
      (node (ref "D3") (pin "C") (pinfunction "C_C") (pintype "passive"))
      (node (ref "IC4") (pin "7") (pinfunction "+IN_7") (pintype "input"))
      (node (ref "R23") (pin "1") (pinfunction "1_1") (pintype "passive"))
    )
    (net (code "29") (name "Net-(IC4A--IN)") (class "Default")
      (node (ref "IC4") (pin "6") (pinfunction "-IN_6") (pintype "input"))
      (node (ref "R21") (pin "2") (pinfunction "2_2") (pintype "passive"))
      (node (ref "R24") (pin "1") (pinfunction "1_1") (pintype "passive"))
    )
    (net (code "30") (name "Net-(IC4B-+IN)") (class "Default")
      (node (ref "IC4") (pin "5") (pinfunction "+IN_5") (pintype "input"))
      (node (ref "R34") (pin "2") (pinfunction "2_2") (pintype "passive"))
      (node (ref "R36") (pin "1") (pinfunction "1_1") (pintype "passive"))
    )
    (net (code "31") (name "Net-(IC4B--IN)") (class "Default")
      (node (ref "D7") (pin "C") (pinfunction "C_C") (pintype "passive"))
      (node (ref "IC4") (pin "4") (pinfunction "-IN_4") (pintype "input"))
      (node (ref "R35") (pin "2") (pinfunction "2_2") (pintype "passive"))
    )
    (net (code "32") (name "Net-(IC4C-+IN)") (class "Default")
      (node (ref "D2") (pin "C") (pinfunction "C_C") (pintype "passive"))
      (node (ref "IC4") (pin "9") (pinfunction "+IN_9") (pintype "input"))
      (node (ref "R14") (pin "1") (pinfunction "1_1") (pintype "passive"))
    )
    (net (code "33") (name "Net-(IC4C--IN)") (class "Default")
      (node (ref "D1") (pin "C") (pinfunction "C_C") (pintype "passive"))
      (node (ref "IC4") (pin "8") (pinfunction "-IN_8") (pintype "input"))
      (node (ref "R15") (pin "1") (pinfunction "1_1") (pintype "passive"))
    )
    (net (code "34") (name "Net-(IC5-RS)") (class "Default")
      (node (ref "IC5") (pin "8") (pinfunction "RS_8") (pintype "input"))
      (node (ref "R38") (pin "1") (pinfunction "1_1") (pintype "passive"))
      (node (ref "R41") (pin "1") (pinfunction "1_1") (pintype "passive"))
    )
    (net (code "35") (name "Net-(Q1-D)") (class "Default")
      (node (ref "Q1") (pin "3") (pinfunction "D_3") (pintype "passive"))
      (node (ref "R5") (pin "2") (pinfunction "2_2") (pintype "passive"))
    )
    (net (code "36") (name "Net-(Q2-D)") (class "Default")
      (node (ref "Q2") (pin "3") (pinfunction "D_3") (pintype "passive"))
      (node (ref "R9") (pin "P$2") (pinfunction "2_P$2") (pintype "passive"))
    )
    (net (code "37") (name "Net-(Q3-D)") (class "Default")
      (node (ref "Q3") (pin "3") (pinfunction "D_3") (pintype "passive"))
      (node (ref "R16") (pin "1") (pinfunction "1_1") (pintype "passive"))
      (node (ref "R19") (pin "2") (pinfunction "2_2") (pintype "passive"))
    )
    (net (code "38") (name "Net-(Q4-D)") (class "Default")
      (node (ref "D4") (pin "A") (pinfunction "A_A") (pintype "passive"))
      (node (ref "Q4") (pin "3") (pinfunction "D_3") (pintype "passive"))
    )
    (net (code "39") (name "Net-(Q4-G)") (class "Default")
      (node (ref "Q4") (pin "1") (pinfunction "G_1") (pintype "passive"))
      (node (ref "Q5") (pin "3") (pinfunction "D_3") (pintype "passive"))
      (node (ref "R22") (pin "2") (pinfunction "2_2") (pintype "passive"))
    )
    (net (code "40") (name "Net-(Q7-B)") (class "Default")
      (node (ref "Q7") (pin "1") (pinfunction "B_1") (pintype "passive"))
      (node (ref "R29") (pin "2") (pinfunction "2_2") (pintype "passive"))
    )
    (net (code "41") (name "Net-(Q8-D)") (class "Default")
      (node (ref "Q8") (pin "3") (pinfunction "D_3") (pintype "passive"))
      (node (ref "R30") (pin "2") (pinfunction "2_2") (pintype "passive"))
      (node (ref "R31") (pin "2") (pinfunction "2_2") (pintype "passive"))
    )
    (net (code "42") (name "Net-(Q9-B)") (class "Default")
      (node (ref "Q9") (pin "1") (pinfunction "B_1") (pintype "passive"))
      (node (ref "R32") (pin "2") (pinfunction "2_2") (pintype "passive"))
    )
    (net (code "43") (name "Net-(Q10-D)") (class "Default")
      (node (ref "Q10") (pin "3") (pinfunction "D_3") (pintype "passive"))
      (node (ref "R41") (pin "2") (pinfunction "2_2") (pintype "passive"))
    )
    (net (code "44") (name "PWM_RX") (class "Default")
      (node (ref "CN1") (pin "20") (pinfunction "20_20") (pintype "passive"))
      (node (ref "IC4") (pin "14") (pinfunction "OUT_14") (pintype "open_collector"))
      (node (ref "R13") (pin "2") (pinfunction "2_2") (pintype "passive"))
    )
    (net (code "45") (name "PWM{slash}~{VPW}") (class "Default")
      (node (ref "CN1") (pin "18") (pinfunction "18_18") (pintype "passive"))
      (node (ref "Q3") (pin "1") (pinfunction "G_1") (pintype "passive"))
      (node (ref "R18") (pin "2") (pinfunction "2_2") (pintype "passive"))
    )
    (net (code "46") (name "PWR_SAVE") (class "Default")
      (node (ref "CN1") (pin "32") (pinfunction "32_32") (pintype "passive"))
      (node (ref "Q8") (pin "1") (pinfunction "G_1") (pintype "passive"))
    )
    (net (code "47") (name "SW_CAN") (class "Default")
      (node (ref "C5") (pin "2") (pinfunction "2_2") (pintype "passive"))
      (node (ref "CN1") (pin "41") (pinfunction "41_41") (pintype "passive"))
      (node (ref "IC2") (pin "7") (pinfunction "CANH_7") (pintype "bidirectional"))
      (node (ref "R8") (pin "1") (pinfunction "1_1") (pintype "passive"))
      (node (ref "R9") (pin "P$1") (pinfunction "1_P$1") (pintype "passive"))
    )
    (net (code "48") (name "SW_CAN_LOAD") (class "Default")
      (node (ref "CN1") (pin "6") (pinfunction "6_6") (pintype "passive"))
      (node (ref "Q2") (pin "1") (pinfunction "G_1") (pintype "passive"))
      (node (ref "R12") (pin "1") (pinfunction "1_1") (pintype "passive"))
    )
    (net (code "49") (name "SW_CAN_MODE0") (class "Default")
      (node (ref "CN1") (pin "4") (pinfunction "4_4") (pintype "passive"))
      (node (ref "IC2") (pin "2") (pinfunction "MODE0_2") (pintype "input"))
      (node (ref "R11") (pin "1") (pinfunction "1_1") (pintype "passive"))
    )
    (net (code "50") (name "SW_CAN_MODE1") (class "Default")
      (node (ref "CN1") (pin "5") (pinfunction "5_5") (pintype "passive"))
      (node (ref "IC2") (pin "3") (pinfunction "MODE1_3") (pintype "input"))
      (node (ref "R10") (pin "1") (pinfunction "1_1") (pintype "passive"))
    )
    (net (code "51") (name "SW_CAN_RX") (class "Default")
      (node (ref "CN1") (pin "2") (pinfunction "2_2") (pintype "passive"))
      (node (ref "IC2") (pin "4") (pinfunction "ROUT_4") (pintype "output"))
      (node (ref "R7") (pin "2") (pinfunction "2_2") (pintype "passive"))
    )
    (net (code "52") (name "SW_CAN_TX") (class "Default")
      (node (ref "CN1") (pin "3") (pinfunction "3_3") (pintype "passive"))
      (node (ref "IC2") (pin "1") (pinfunction "TIN_1") (pintype "input"))
    )
    (net (code "53") (name "VPW_RX") (class "Default")
      (node (ref "CN1") (pin "19") (pinfunction "19_19") (pintype "passive"))
      (node (ref "IC4") (pin "1") (pinfunction "OUT_1") (pintype "open_collector"))
      (node (ref "R20") (pin "2") (pinfunction "2_2") (pintype "passive"))
    )
    (net (code "54") (name "unconnected-(CN1-Pad11)") (class "Default")
      (node (ref "CN1") (pin "11") (pinfunction "11_11") (pintype "passive"))
    )
    (net (code "55") (name "unconnected-(CN1-Pad34)") (class "Default")
      (node (ref "CN1") (pin "34") (pinfunction "34_34") (pintype "passive"))
    )
    (net (code "56") (name "unconnected-(CN1-Pad36)") (class "Default")
      (node (ref "CN1") (pin "36") (pinfunction "36_36") (pintype "passive"))
    )
    (net (code "57") (name "unconnected-(CN1-Pad40)") (class "Default")
      (node (ref "CN1") (pin "40") (pinfunction "40_40") (pintype "passive"))
    )
    (net (code "58") (name "unconnected-(CN1-Pad42)") (class "Default")
      (node (ref "CN1") (pin "42") (pinfunction "42_42") (pintype "passive"))
    )
    (net (code "59") (name "unconnected-(IC1-VREF-Pad5)") (class "Default")
      (node (ref "IC1") (pin "5") (pinfunction "VREF_5") (pintype "output"))
    )
    (net (code "60") (name "unconnected-(IC5-VREF-Pad5)") (class "Default")
      (node (ref "IC5") (pin "5") (pinfunction "VREF_5") (pintype "output"))
    )
    (net (code "61") (name "~{ISO_K_TX}") (class "Default")
      (node (ref "CN1") (pin "16") (pinfunction "16_16") (pintype "passive"))
      (node (ref "R32") (pin "1") (pinfunction "1_1") (pintype "passive"))
    )
    (net (code "62") (name "~{ISO_L_TX}") (class "Default")
      (node (ref "CN1") (pin "17") (pinfunction "17_17") (pintype "passive"))
      (node (ref "R29") (pin "1") (pinfunction "1_1") (pintype "passive"))
    )
    (net (code "63") (name "~{ISO_RX}") (class "Default")
      (node (ref "CN1") (pin "15") (pinfunction "15_15") (pintype "passive"))
      (node (ref "IC4") (pin "2") (pinfunction "OUT_2") (pintype "open_collector"))
      (node (ref "R33") (pin "2") (pinfunction "2_2") (pintype "passive"))
    )
    (net (code "64") (name "~{J1850_BUS-_TX}") (class "Default")
      (node (ref "CN1") (pin "21") (pinfunction "21_21") (pintype "passive"))
      (node (ref "Q6") (pin "1") (pinfunction "G_1") (pintype "passive"))
      (node (ref "R28") (pin "2") (pinfunction "2_2") (pintype "passive"))
    )
    (net (code "65") (name "~{J1850_BUS-}") (class "Default")
      (node (ref "CN1") (pin "26") (pinfunction "26_26") (pintype "passive"))
      (node (ref "Q6") (pin "3") (pinfunction "D_3") (pintype "passive"))
      (node (ref "R15") (pin "2") (pinfunction "2_2") (pintype "passive"))
      (node (ref "R27") (pin "2") (pinfunction "2_2") (pintype "passive"))
    )
    (net (code "66") (name "~{PWR_SAVE}") (class "Default")
      (node (ref "CN1") (pin "14") (pinfunction "14_14") (pintype "passive"))
      (node (ref "CN1") (pin "9") (pinfunction "9_9") (pintype "passive"))
      (node (ref "Q1") (pin "1") (pinfunction "G_1") (pintype "passive"))
      (node (ref "Q10") (pin "1") (pinfunction "G_1") (pintype "passive"))
      (node (ref "R42") (pin "2") (pinfunction "2_2") (pintype "passive"))
      (node (ref "R6") (pin "2") (pinfunction "2_2") (pintype "passive"))
    )
  )
)
